# DPPXHK_MCU.net
KiCad netlist of a schematic drawn in Altium Designer
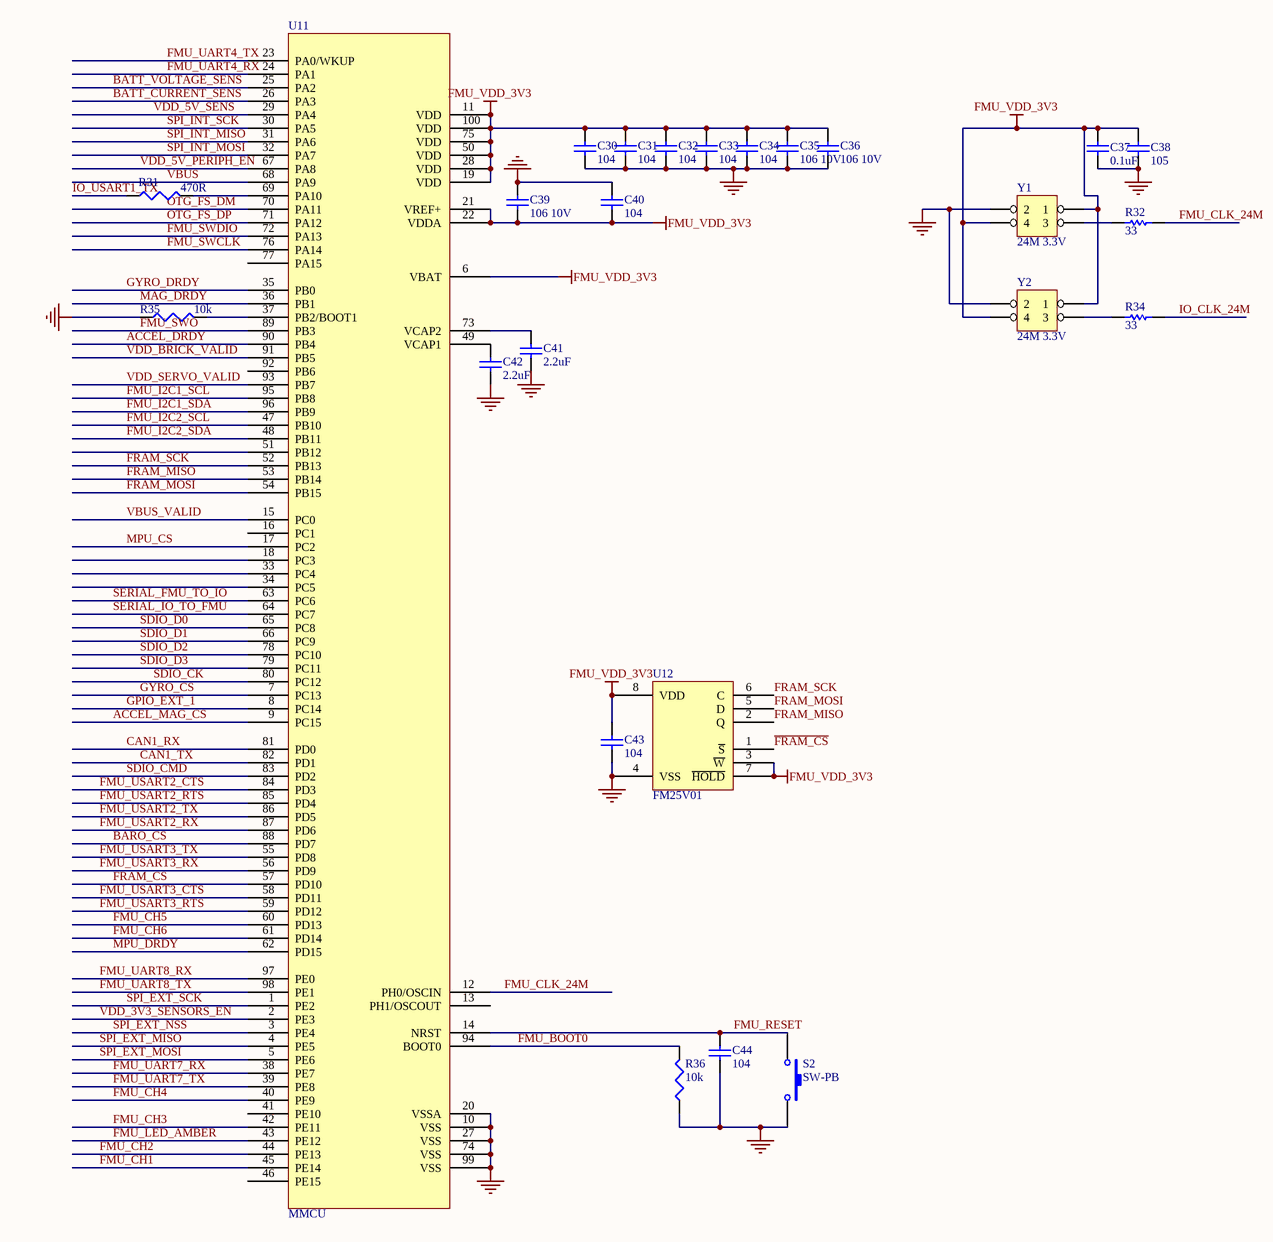
[diagram p0: DPPXHK_MCU.SchDoc]

(export (version "E")
  (design (tool "Eeschema 10.0.6"))
  (components
    (comp (ref "C30")
      (value "104")
      (footprint "LC0402")
      (description "Capacitor (Semiconductor SIM Model)")
      (fields (field (name "PUBLISHER") "Altium Limited"))
      (libsource (lib "Miscellaneous Devices") (part "Cap Semi"))
    )
    (comp (ref "C31")
      (value "104")
      (footprint "LC0402")
      (description "Capacitor (Semiconductor SIM Model)")
      (fields (field (name "PUBLISHER") "Altium Limited"))
      (libsource (lib "Miscellaneous Devices") (part "Cap Semi"))
    )
    (comp (ref "C32")
      (value "104")
      (footprint "LC0402")
      (description "Capacitor (Semiconductor SIM Model)")
      (fields (field (name "PUBLISHER") "Altium Limited"))
      (libsource (lib "Miscellaneous Devices") (part "Cap Semi"))
    )
    (comp (ref "C33")
      (value "104")
      (footprint "LC0402")
      (description "Capacitor (Semiconductor SIM Model)")
      (fields (field (name "PUBLISHER") "Altium Limited"))
      (libsource (lib "Miscellaneous Devices") (part "Cap Semi"))
    )
    (comp (ref "C34")
      (value "104")
      (footprint "LC0402")
      (description "Capacitor (Semiconductor SIM Model)")
      (fields (field (name "PUBLISHER") "Altium Limited"))
      (libsource (lib "Miscellaneous Devices") (part "Cap Semi"))
    )
    (comp (ref "C35")
      (value "106 10V")
      (footprint "LC0402")
      (description "Capacitor (Semiconductor SIM Model)")
      (fields (field (name "PUBLISHER") "Altium Limited"))
      (libsource (lib "Miscellaneous Devices") (part "Cap Semi"))
    )
    (comp (ref "C36")
      (value "106 10V")
      (footprint "LC0402")
      (description "Capacitor (Semiconductor SIM Model)")
      (fields (field (name "PUBLISHER") "Altium Limited"))
      (libsource (lib "Miscellaneous Devices") (part "Cap Semi"))
    )
    (comp (ref "C37")
      (value "0.1uF")
      (footprint "LC0402")
      (description "Capacitor (Semiconductor SIM Model)")
      (fields (field (name "Comment") "104") (field (name "PUBLISHER") "Altium Limited"))
      (libsource (lib "*") (part "Cap Semi"))
    )
    (comp (ref "C38")
      (value "105")
      (footprint "LC0402")
      (description "Capacitor (Semiconductor SIM Model)")
      (fields (field (name "PUBLISHER") "Altium Limited"))
      (libsource (lib "*") (part "Cap Semi"))
    )
    (comp (ref "C39")
      (value "106 10V")
      (footprint "LC0402")
      (description "Capacitor (Semiconductor SIM Model)")
      (fields (field (name "PUBLISHER") "Altium Limited"))
      (libsource (lib "Miscellaneous Devices") (part "Cap Semi"))
    )
    (comp (ref "C40")
      (value "104")
      (footprint "LC0402")
      (description "Capacitor (Semiconductor SIM Model)")
      (fields (field (name "PUBLISHER") "Altium Limited"))
      (libsource (lib "Miscellaneous Devices") (part "Cap Semi"))
    )
    (comp (ref "C41")
      (value "2.2uF")
      (footprint "LC0402")
      (description "Capacitor (Semiconductor SIM Model)")
      (fields (field (name "PUBLISHER") "Altium Limited"))
      (libsource (lib "Miscellaneous Devices") (part "Cap Semi"))
    )
    (comp (ref "C42")
      (value "2.2uF")
      (footprint "LC0402")
      (description "Capacitor (Semiconductor SIM Model)")
      (fields (field (name "PUBLISHER") "Altium Limited"))
      (libsource (lib "Miscellaneous Devices") (part "Cap Semi"))
    )
    (comp (ref "C43")
      (value "104")
      (footprint "LC0402")
      (description "Capacitor (Semiconductor SIM Model)")
      (fields (field (name "PUBLISHER") "Altium Limited"))
      (libsource (lib "Miscellaneous Devices") (part "Cap Semi"))
    )
    (comp (ref "C44")
      (value "104")
      (footprint "LC0402")
      (description "Capacitor (Semiconductor SIM Model)")
      (fields (field (name "PUBLISHER") "Altium Limited"))
      (libsource (lib "Miscellaneous Devices") (part "Cap Semi"))
    )
    (comp (ref "R31")
      (value "470R")
      (footprint "0402R")
      (description "Resistor")
      (fields (field (name "PUBLISHER") "Altium Limited"))
      (libsource (lib "Miscellaneous Devices") (part "Res3"))
    )
    (comp (ref "R32")
      (value "33")
      (footprint "0402R")
      (description "Resistor")
      (fields
        (field (name "MANUFACTURER") "Generic Components")
        (field (name "Comment") "33R")
        (field (name "PUBLISHER") "Altium Hobart Technology Centre")
      )
      (libsource (lib "*") (part "Res1"))
    )
    (comp (ref "R34")
      (value "33")
      (footprint "0402R")
      (description "Resistor")
      (fields
        (field (name "MANUFACTURER") "Generic Components")
        (field (name "Comment") "33R")
        (field (name "PUBLISHER") "Altium Hobart Technology Centre")
      )
      (libsource (lib "*") (part "Res1"))
    )
    (comp (ref "R35")
      (value "10k")
      (footprint "0402R")
      (description "Resistor")
      (fields (field (name "PUBLISHER") "Altium Limited"))
      (libsource (lib "Miscellaneous Devices") (part "Res3"))
    )
    (comp (ref "R36")
      (value "10k")
      (footprint "0402R")
      (description "Resistor")
      (fields (field (name "PUBLISHER") "Altium Limited"))
      (libsource (lib "Miscellaneous Devices") (part "Res3"))
    )
    (comp (ref "S2")
      (value "SW-PB")
      (footprint "BUTTON-3*6")
      (description "Switch")
      (fields (field (name "PUBLISHER") "Altium Limited"))
      (libsource (lib "Miscellaneous Devices") (part "SW-PB"))
    )
    (comp (ref "U11") (value "MMCU") (footprint "LQFP100st") (libsource (lib "*") (part "F4x7")))
    (comp (ref "U12") (value "FM25V01") (footprint "SO-g8") (libsource (lib "PXHK") (part "FM25V01")))
    (comp (ref "Y1")
      (value "24M 3.3V")
      (footprint "OSCILLATOR-3.2X2.5")
      (libsource (lib "*") (part "HEADER 2X2"))
    )
    (comp (ref "Y2")
      (value "24M 3.3V")
      (footprint "OSCILLATOR-3.2X2.5")
      (libsource (lib "*") (part "HEADER 2X2"))
    )
  )
  (nets
    (net (code "1") (name "/ACCEL_DRDY") (class "Default")
      (node (ref "U11") (pin "90") (pinfunction "PB4_90") (pintype "passive"))
    )
    (net (code "2") (name "/ACCEL_MAG_CS") (class "Default")
      (node (ref "U11") (pin "9") (pinfunction "PC15_9") (pintype "passive"))
    )
    (net (code "3") (name "/BARO_CS") (class "Default")
      (node (ref "U11") (pin "88") (pinfunction "PD7_88") (pintype "passive"))
    )
    (net (code "4") (name "/BATT_CURRENT_SENS") (class "Default")
      (node (ref "U11") (pin "26") (pinfunction "PA3_26") (pintype "passive"))
    )
    (net (code "5") (name "/BATT_VOLTAGE_SENS") (class "Default")
      (node (ref "U11") (pin "25") (pinfunction "PA2_25") (pintype "passive"))
    )
    (net (code "6") (name "/CAN1_RX") (class "Default")
      (node (ref "U11") (pin "81") (pinfunction "PD0_81") (pintype "passive"))
    )
    (net (code "7") (name "/CAN1_TX") (class "Default")
      (node (ref "U11") (pin "82") (pinfunction "PD1_82") (pintype "passive"))
    )
    (net (code "8") (name "/FMU_BOOT0") (class "Default")
      (node (ref "R36") (pin "2") (pinfunction "2_2") (pintype "passive"))
      (node (ref "U11") (pin "94") (pinfunction "BOOT0_94") (pintype "passive"))
    )
    (net (code "9") (name "/FMU_CH1") (class "Default")
      (node (ref "U11") (pin "45") (pinfunction "PE14_45") (pintype "passive"))
    )
    (net (code "10") (name "/FMU_CH2") (class "Default")
      (node (ref "U11") (pin "44") (pinfunction "PE13_44") (pintype "passive"))
    )
    (net (code "11") (name "/FMU_CH3") (class "Default")
      (node (ref "U11") (pin "42") (pinfunction "PE11_42") (pintype "passive"))
    )
    (net (code "12") (name "/FMU_CH4") (class "Default")
      (node (ref "U11") (pin "40") (pinfunction "PE9_40") (pintype "passive"))
    )
    (net (code "13") (name "/FMU_CH5") (class "Default")
      (node (ref "U11") (pin "60") (pinfunction "PD13_60") (pintype "passive"))
    )
    (net (code "14") (name "/FMU_CH6") (class "Default")
      (node (ref "U11") (pin "61") (pinfunction "PD14_61") (pintype "passive"))
    )
    (net (code "15") (name "/FMU_CLK_24M") (class "Default")
      (node (ref "R32") (pin "2") (pinfunction "2_2") (pintype "passive"))
      (node (ref "U11") (pin "12") (pinfunction "PH0/OSCIN_12") (pintype "passive"))
    )
    (net (code "16") (name "/FMU_I2C1_SCL") (class "Default")
      (node (ref "U11") (pin "95") (pinfunction "PB8_95") (pintype "passive"))
    )
    (net (code "17") (name "/FMU_I2C1_SDA") (class "Default")
      (node (ref "U11") (pin "96") (pinfunction "PB9_96") (pintype "passive"))
    )
    (net (code "18") (name "/FMU_I2C2_SCL") (class "Default")
      (node (ref "U11") (pin "47") (pinfunction "PB10_47") (pintype "passive"))
    )
    (net (code "19") (name "/FMU_I2C2_SDA") (class "Default")
      (node (ref "U11") (pin "48") (pinfunction "PB11_48") (pintype "passive"))
    )
    (net (code "20") (name "/FMU_LED_AMBER") (class "Default")
      (node (ref "U11") (pin "43") (pinfunction "PE12_43") (pintype "passive"))
    )
    (net (code "21") (name "/FMU_RESET") (class "Default")
      (node (ref "C44") (pin "2") (pinfunction "2_2") (pintype "passive"))
      (node (ref "S2") (pin "1") (pinfunction "1_1") (pintype "passive"))
      (node (ref "U11") (pin "14") (pinfunction "NRST_14") (pintype "passive"))
    )
    (net (code "22") (name "/FMU_SWCLK") (class "Default")
      (node (ref "U11") (pin "76") (pinfunction "PA14_76") (pintype "passive"))
    )
    (net (code "23") (name "/FMU_SWDIO") (class "Default")
      (node (ref "U11") (pin "72") (pinfunction "PA13_72") (pintype "passive"))
    )
    (net (code "24") (name "/FMU_SWO") (class "Default")
      (node (ref "U11") (pin "89") (pinfunction "PB3_89") (pintype "passive"))
    )
    (net (code "25") (name "/FMU_UART4_RX") (class "Default")
      (node (ref "U11") (pin "24") (pinfunction "PA1_24") (pintype "passive"))
    )
    (net (code "26") (name "/FMU_UART4_TX") (class "Default")
      (node (ref "U11") (pin "23") (pinfunction "PA0/WKUP_23") (pintype "passive"))
    )
    (net (code "27") (name "/FMU_UART7_RX") (class "Default")
      (node (ref "U11") (pin "38") (pinfunction "PE7_38") (pintype "passive"))
    )
    (net (code "28") (name "/FMU_UART7_TX") (class "Default")
      (node (ref "U11") (pin "39") (pinfunction "PE8_39") (pintype "passive"))
    )
    (net (code "29") (name "/FMU_UART8_RX") (class "Default")
      (node (ref "U11") (pin "97") (pinfunction "PE0_97") (pintype "passive"))
    )
    (net (code "30") (name "/FMU_UART8_TX") (class "Default")
      (node (ref "U11") (pin "98") (pinfunction "PE1_98") (pintype "passive"))
    )
    (net (code "31") (name "/FMU_USART2_CTS") (class "Default")
      (node (ref "U11") (pin "84") (pinfunction "PD3_84") (pintype "passive"))
    )
    (net (code "32") (name "/FMU_USART2_RTS") (class "Default")
      (node (ref "U11") (pin "85") (pinfunction "PD4_85") (pintype "passive"))
    )
    (net (code "33") (name "/FMU_USART2_RX") (class "Default")
      (node (ref "U11") (pin "87") (pinfunction "PD6_87") (pintype "passive"))
    )
    (net (code "34") (name "/FMU_USART2_TX") (class "Default")
      (node (ref "U11") (pin "86") (pinfunction "PD5_86") (pintype "passive"))
    )
    (net (code "35") (name "/FMU_USART3_CTS") (class "Default")
      (node (ref "U11") (pin "58") (pinfunction "PD11_58") (pintype "passive"))
    )
    (net (code "36") (name "/FMU_USART3_RTS") (class "Default")
      (node (ref "U11") (pin "59") (pinfunction "PD12_59") (pintype "passive"))
    )
    (net (code "37") (name "/FMU_USART3_RX") (class "Default")
      (node (ref "U11") (pin "56") (pinfunction "PD9_56") (pintype "passive"))
    )
    (net (code "38") (name "/FMU_USART3_TX") (class "Default")
      (node (ref "U11") (pin "55") (pinfunction "PD8_55") (pintype "passive"))
    )
    (net (code "39") (name "/FRAM_MISO") (class "Default")
      (node (ref "U11") (pin "53") (pinfunction "PB14_53") (pintype "passive"))
      (node (ref "U12") (pin "2") (pinfunction "Q_2") (pintype "passive"))
    )
    (net (code "40") (name "/FRAM_MOSI") (class "Default")
      (node (ref "U11") (pin "54") (pinfunction "PB15_54") (pintype "passive"))
      (node (ref "U12") (pin "5") (pinfunction "D_5") (pintype "passive"))
    )
    (net (code "41") (name "/FRAM_SCK") (class "Default")
      (node (ref "U11") (pin "52") (pinfunction "PB13_52") (pintype "passive"))
      (node (ref "U12") (pin "6") (pinfunction "C_6") (pintype "passive"))
    )
    (net (code "42") (name "/GPIO_EXT_1") (class "Default")
      (node (ref "U11") (pin "8") (pinfunction "PC14_8") (pintype "passive"))
    )
    (net (code "43") (name "/GYRO_CS") (class "Default")
      (node (ref "U11") (pin "7") (pinfunction "PC13_7") (pintype "passive"))
    )
    (net (code "44") (name "/GYRO_DRDY") (class "Default")
      (node (ref "U11") (pin "35") (pinfunction "PB0_35") (pintype "passive"))
    )
    (net (code "45") (name "/IO_CLK_24M") (class "Default")
      (node (ref "R34") (pin "2") (pinfunction "2_2") (pintype "passive"))
    )
    (net (code "46") (name "/IO_USART1_TX") (class "Default")
      (node (ref "R31") (pin "1") (pinfunction "1_1") (pintype "passive"))
    )
    (net (code "47") (name "/MAG_DRDY") (class "Default")
      (node (ref "U11") (pin "36") (pinfunction "PB1_36") (pintype "passive"))
    )
    (net (code "48") (name "/MPU_CS") (class "Default")
      (node (ref "U11") (pin "17") (pinfunction "PC2_17") (pintype "passive"))
    )
    (net (code "49") (name "/MPU_DRDY") (class "Default")
      (node (ref "U11") (pin "62") (pinfunction "PD15_62") (pintype "passive"))
    )
    (net (code "50") (name "/OTG_FS_DM") (class "Default")
      (node (ref "U11") (pin "70") (pinfunction "PA11_70") (pintype "passive"))
    )
    (net (code "51") (name "/OTG_FS_DP") (class "Default")
      (node (ref "U11") (pin "71") (pinfunction "PA12_71") (pintype "passive"))
    )
    (net (code "52") (name "/SDIO_CK") (class "Default")
      (node (ref "U11") (pin "80") (pinfunction "PC12_80") (pintype "passive"))
    )
    (net (code "53") (name "/SDIO_CMD") (class "Default")
      (node (ref "U11") (pin "83") (pinfunction "PD2_83") (pintype "passive"))
    )
    (net (code "54") (name "/SDIO_D0") (class "Default")
      (node (ref "U11") (pin "65") (pinfunction "PC8_65") (pintype "passive"))
    )
    (net (code "55") (name "/SDIO_D1") (class "Default")
      (node (ref "U11") (pin "66") (pinfunction "PC9_66") (pintype "passive"))
    )
    (net (code "56") (name "/SDIO_D2") (class "Default")
      (node (ref "U11") (pin "78") (pinfunction "PC10_78") (pintype "passive"))
    )
    (net (code "57") (name "/SDIO_D3") (class "Default")
      (node (ref "U11") (pin "79") (pinfunction "PC11_79") (pintype "passive"))
    )
    (net (code "58") (name "/SERIAL_FMU_TO_IO") (class "Default")
      (node (ref "U11") (pin "63") (pinfunction "PC6_63") (pintype "passive"))
    )
    (net (code "59") (name "/SERIAL_IO_TO_FMU") (class "Default")
      (node (ref "U11") (pin "64") (pinfunction "PC7_64") (pintype "passive"))
    )
    (net (code "60") (name "/SPI_EXT_MISO") (class "Default")
      (node (ref "U11") (pin "4") (pinfunction "PE5_4") (pintype "passive"))
    )
    (net (code "61") (name "/SPI_EXT_MOSI") (class "Default")
      (node (ref "U11") (pin "5") (pinfunction "PE6_5") (pintype "passive"))
    )
    (net (code "62") (name "/SPI_EXT_NSS") (class "Default")
      (node (ref "U11") (pin "3") (pinfunction "PE4_3") (pintype "passive"))
    )
    (net (code "63") (name "/SPI_EXT_SCK") (class "Default")
      (node (ref "U11") (pin "1") (pinfunction "PE2_1") (pintype "passive"))
    )
    (net (code "64") (name "/SPI_INT_MISO") (class "Default")
      (node (ref "U11") (pin "31") (pinfunction "PA6_31") (pintype "passive"))
    )
    (net (code "65") (name "/SPI_INT_MOSI") (class "Default")
      (node (ref "U11") (pin "32") (pinfunction "PA7_32") (pintype "passive"))
    )
    (net (code "66") (name "/SPI_INT_SCK") (class "Default")
      (node (ref "U11") (pin "30") (pinfunction "PA5_30") (pintype "passive"))
    )
    (net (code "67") (name "/VBUS") (class "Default")
      (node (ref "U11") (pin "68") (pinfunction "PA9_68") (pintype "passive"))
    )
    (net (code "68") (name "/VBUS_VALID") (class "Default")
      (node (ref "U11") (pin "15") (pinfunction "PC0_15") (pintype "passive"))
    )
    (net (code "69") (name "/VDD_3V3_SENSORS_EN") (class "Default")
      (node (ref "U11") (pin "2") (pinfunction "PE3_2") (pintype "passive"))
    )
    (net (code "70") (name "/VDD_5V_PERIPH_EN") (class "Default")
      (node (ref "U11") (pin "67") (pinfunction "PA8_67") (pintype "passive"))
    )
    (net (code "71") (name "/VDD_5V_SENS") (class "Default")
      (node (ref "U11") (pin "29") (pinfunction "PA4_29") (pintype "passive"))
    )
    (net (code "72") (name "/VDD_BRICK_VALID") (class "Default")
      (node (ref "U11") (pin "91") (pinfunction "PB5_91") (pintype "passive"))
    )
    (net (code "73") (name "/VDD_SERVO_VALID") (class "Default")
      (node (ref "U11") (pin "93") (pinfunction "PB7_93") (pintype "passive"))
    )
    (net (code "74") (name "/~{FRAM_CS}") (class "Default")
      (node (ref "U11") (pin "57") (pinfunction "PD10_57") (pintype "passive"))
      (node (ref "U12") (pin "1") (pinfunction "~{S}_1") (pintype "passive"))
    )
    (net (code "75") (name "FMU_VDD_3V3") (class "Default")
      (node (ref "C30") (pin "1") (pinfunction "1_1") (pintype "passive"))
      (node (ref "C31") (pin "1") (pinfunction "1_1") (pintype "passive"))
      (node (ref "C32") (pin "1") (pinfunction "1_1") (pintype "passive"))
      (node (ref "C33") (pin "1") (pinfunction "1_1") (pintype "passive"))
      (node (ref "C34") (pin "1") (pinfunction "1_1") (pintype "passive"))
      (node (ref "C35") (pin "1") (pinfunction "1_1") (pintype "passive"))
      (node (ref "C36") (pin "1") (pinfunction "1_1") (pintype "passive"))
      (node (ref "C37") (pin "2") (pinfunction "2_2") (pintype "passive"))
      (node (ref "C38") (pin "2") (pinfunction "2_2") (pintype "passive"))
      (node (ref "C39") (pin "2") (pinfunction "2_2") (pintype "passive"))
      (node (ref "C40") (pin "2") (pinfunction "2_2") (pintype "passive"))
      (node (ref "C43") (pin "2") (pinfunction "2_2") (pintype "passive"))
      (node (ref "U11") (pin "100") (pinfunction "VDD_100") (pintype "passive"))
      (node (ref "U11") (pin "11") (pinfunction "VDD_11") (pintype "passive"))
      (node (ref "U11") (pin "19") (pinfunction "VDD_19") (pintype "passive"))
      (node (ref "U11") (pin "21") (pinfunction "VREF+_21") (pintype "passive"))
      (node (ref "U11") (pin "22") (pinfunction "VDDA_22") (pintype "passive"))
      (node (ref "U11") (pin "28") (pinfunction "VDD_28") (pintype "passive"))
      (node (ref "U11") (pin "50") (pinfunction "VDD_50") (pintype "passive"))
      (node (ref "U11") (pin "6") (pinfunction "VBAT_6") (pintype "passive"))
      (node (ref "U11") (pin "75") (pinfunction "VDD_75") (pintype "passive"))
      (node (ref "U12") (pin "3") (pinfunction "~{W}_3") (pintype "passive"))
      (node (ref "U12") (pin "7") (pinfunction "~{HOLD}_7") (pintype "passive"))
      (node (ref "U12") (pin "8") (pinfunction "VDD_8") (pintype "passive"))
      (node (ref "Y1") (pin "1") (pinfunction "1_1") (pintype "passive"))
      (node (ref "Y1") (pin "4") (pinfunction "4_4") (pintype "passive"))
      (node (ref "Y2") (pin "1") (pinfunction "1_1") (pintype "passive"))
      (node (ref "Y2") (pin "4") (pinfunction "4_4") (pintype "passive"))
    )
    (net (code "76") (name "GND") (class "Default")
      (node (ref "C30") (pin "2") (pinfunction "2_2") (pintype "passive"))
      (node (ref "C31") (pin "2") (pinfunction "2_2") (pintype "passive"))
      (node (ref "C32") (pin "2") (pinfunction "2_2") (pintype "passive"))
      (node (ref "C33") (pin "2") (pinfunction "2_2") (pintype "passive"))
      (node (ref "C34") (pin "2") (pinfunction "2_2") (pintype "passive"))
      (node (ref "C35") (pin "2") (pinfunction "2_2") (pintype "passive"))
      (node (ref "C36") (pin "2") (pinfunction "2_2") (pintype "passive"))
      (node (ref "C37") (pin "1") (pinfunction "1_1") (pintype "passive"))
      (node (ref "C38") (pin "1") (pinfunction "1_1") (pintype "passive"))
      (node (ref "C39") (pin "1") (pinfunction "1_1") (pintype "passive"))
      (node (ref "C40") (pin "1") (pinfunction "1_1") (pintype "passive"))
      (node (ref "C41") (pin "2") (pinfunction "2_2") (pintype "passive"))
      (node (ref "C42") (pin "2") (pinfunction "2_2") (pintype "passive"))
      (node (ref "C43") (pin "1") (pinfunction "1_1") (pintype "passive"))
      (node (ref "C44") (pin "1") (pinfunction "1_1") (pintype "passive"))
      (node (ref "R35") (pin "1") (pinfunction "1_1") (pintype "passive"))
      (node (ref "R36") (pin "1") (pinfunction "1_1") (pintype "passive"))
      (node (ref "S2") (pin "2") (pinfunction "2_2") (pintype "passive"))
      (node (ref "U11") (pin "10") (pinfunction "VSS_10") (pintype "passive"))
      (node (ref "U11") (pin "20") (pinfunction "VSSA_20") (pintype "passive"))
      (node (ref "U11") (pin "27") (pinfunction "VSS_27") (pintype "passive"))
      (node (ref "U11") (pin "74") (pinfunction "VSS_74") (pintype "passive"))
      (node (ref "U11") (pin "99") (pinfunction "VSS_99") (pintype "passive"))
      (node (ref "U12") (pin "4") (pinfunction "VSS_4") (pintype "passive"))
      (node (ref "Y1") (pin "2") (pinfunction "2_2") (pintype "passive"))
      (node (ref "Y2") (pin "2") (pinfunction "2_2") (pintype "passive"))
    )
    (net (code "77") (name "Net-(R32-Pad1)") (class "Default")
      (node (ref "R32") (pin "1") (pinfunction "1_1") (pintype "passive"))
      (node (ref "Y1") (pin "3") (pinfunction "3_3") (pintype "passive"))
    )
    (net (code "78") (name "Net-(R34-Pad1)") (class "Default")
      (node (ref "R34") (pin "1") (pinfunction "1_1") (pintype "passive"))
      (node (ref "Y2") (pin "3") (pinfunction "3_3") (pintype "passive"))
    )
    (net (code "79") (name "Net-(U11-PA10)") (class "Default")
      (node (ref "R31") (pin "2") (pinfunction "2_2") (pintype "passive"))
      (node (ref "U11") (pin "69") (pinfunction "PA10_69") (pintype "passive"))
    )
    (net (code "80") (name "Net-(U11-PB2{slash}BOOT1)") (class "Default")
      (node (ref "R35") (pin "2") (pinfunction "2_2") (pintype "passive"))
      (node (ref "U11") (pin "37") (pinfunction "PB2/BOOT1_37") (pintype "passive"))
    )
    (net (code "81") (name "Net-(U11-VCAP1)") (class "Default")
      (node (ref "C42") (pin "1") (pinfunction "1_1") (pintype "passive"))
      (node (ref "U11") (pin "49") (pinfunction "VCAP1_49") (pintype "passive"))
    )
    (net (code "82") (name "Net-(U11-VCAP2)") (class "Default")
      (node (ref "C41") (pin "1") (pinfunction "1_1") (pintype "passive"))
      (node (ref "U11") (pin "73") (pinfunction "VCAP2_73") (pintype "passive"))
    )
    (net (code "83") (name "unconnected-(U11-PA15-Pad77)") (class "Default")
      (node (ref "U11") (pin "77") (pinfunction "PA15_77") (pintype "passive"))
    )
    (net (code "84") (name "unconnected-(U11-PB6-Pad92)") (class "Default")
      (node (ref "U11") (pin "92") (pinfunction "PB6_92") (pintype "passive"))
    )
    (net (code "85") (name "unconnected-(U11-PB12-Pad51)") (class "Default")
      (node (ref "U11") (pin "51") (pinfunction "PB12_51") (pintype "passive"))
    )
    (net (code "86") (name "unconnected-(U11-PC1-Pad16)") (class "Default")
      (node (ref "U11") (pin "16") (pinfunction "PC1_16") (pintype "passive"))
    )
    (net (code "87") (name "unconnected-(U11-PC3-Pad18)") (class "Default")
      (node (ref "U11") (pin "18") (pinfunction "PC3_18") (pintype "passive"))
    )
    (net (code "88") (name "unconnected-(U11-PC4-Pad33)") (class "Default")
      (node (ref "U11") (pin "33") (pinfunction "PC4_33") (pintype "passive"))
    )
    (net (code "89") (name "unconnected-(U11-PC5-Pad34)") (class "Default")
      (node (ref "U11") (pin "34") (pinfunction "PC5_34") (pintype "passive"))
    )
    (net (code "90") (name "unconnected-(U11-PE10-Pad41)") (class "Default")
      (node (ref "U11") (pin "41") (pinfunction "PE10_41") (pintype "passive"))
    )
    (net (code "91") (name "unconnected-(U11-PE15-Pad46)") (class "Default")
      (node (ref "U11") (pin "46") (pinfunction "PE15_46") (pintype "passive"))
    )
    (net (code "92") (name "unconnected-(U11-PH1{slash}OSCOUT-Pad13)") (class "Default")
      (node (ref "U11") (pin "13") (pinfunction "PH1/OSCOUT_13") (pintype "passive"))
    )
  )
)
